# Connectors.net
KiCad netlist of a schematic drawn in Altium Designer
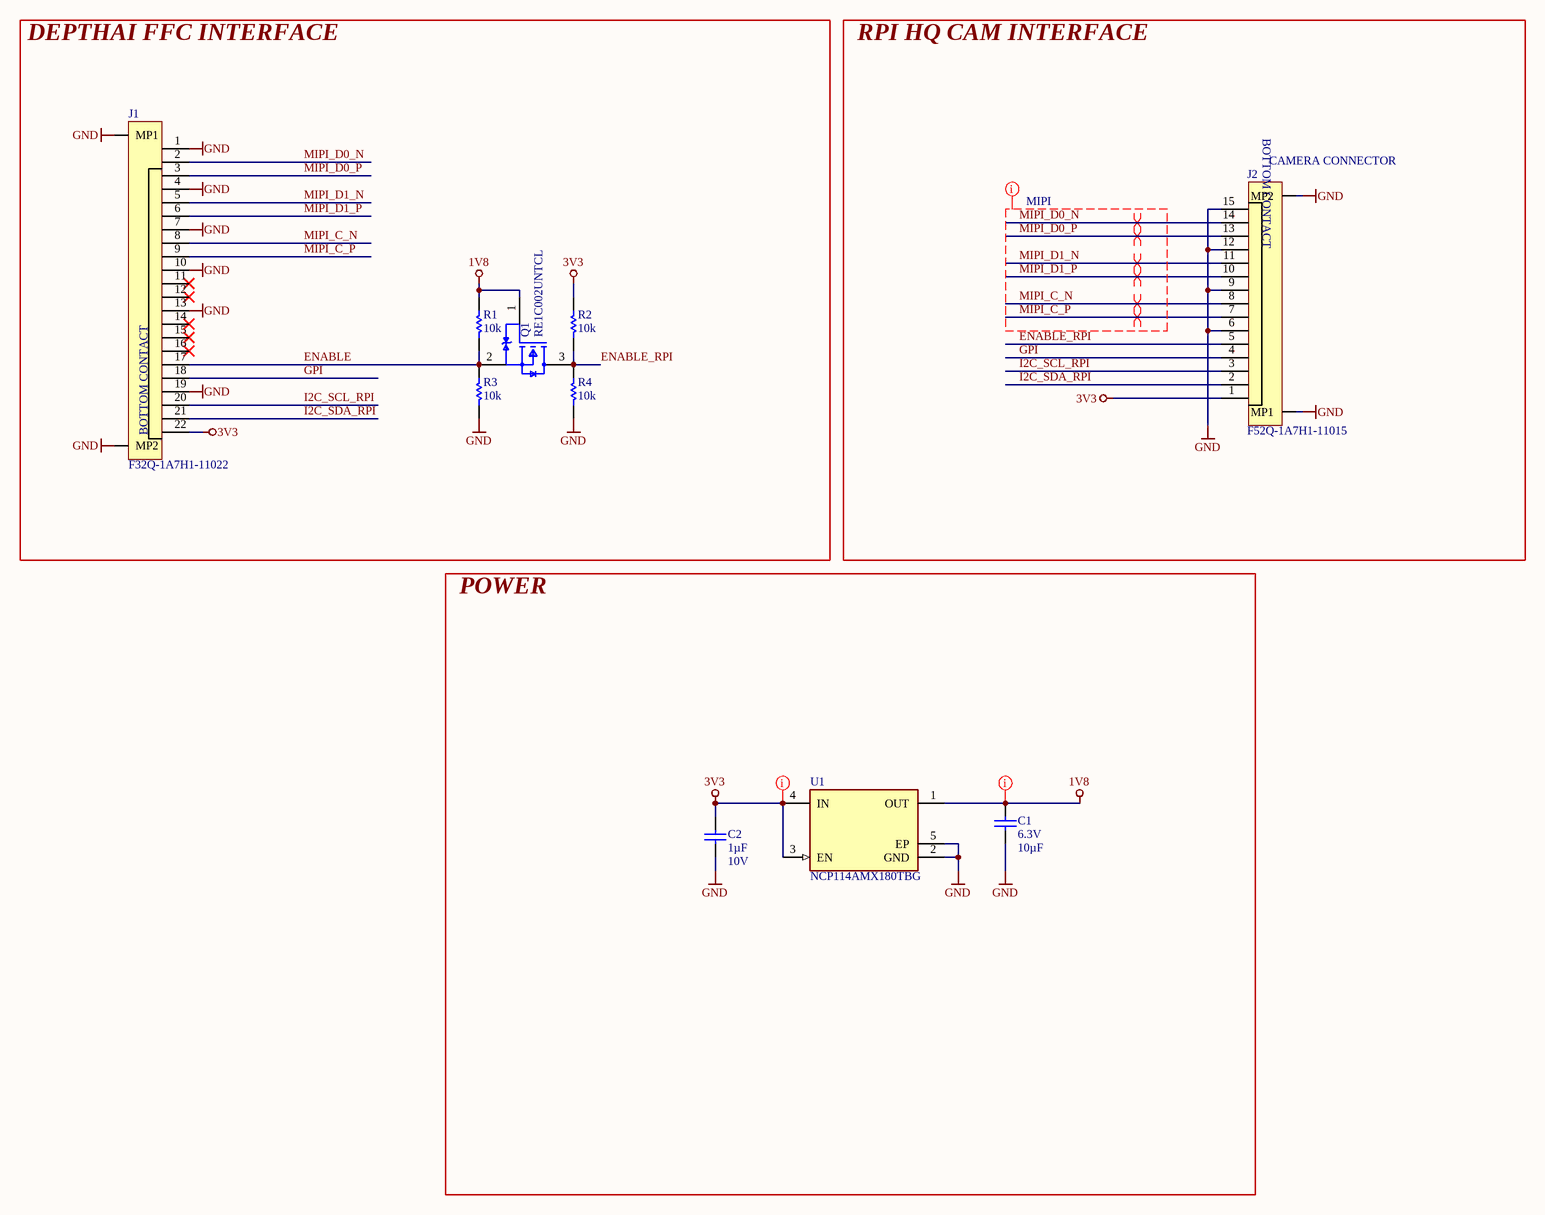
[diagram p0: Connectors.SchDoc]

(export (version "E")
  (design (tool "Eeschema 10.0.6"))
  (components
    (comp (ref "C1")
      (value "10µF")
      (footprint "CAPC0402(1005)70_L")
      (description "CAP CER 10UF 6.3V X5R 0402 20%")
      (fields
        (field (name "TOLERANCE") "20%")
        (field (name "VOLTAGE RATING") "6.3V")
        (field (name "Comment") "GRM155R60J106ME15D")
      )
      (libsource (lib "Luxonis LLC") (part "LLL153C70G474ME17E"))
    )
    (comp (ref "C2")
      (value "1µF")
      (footprint "CAPC0201(0603)33_L")
      (description "CAP CER 1UF 10V X5R 0201 20%")
      (fields
        (field (name "VOLTAGE RATING") "10V")
        (field (name "TOLERANCE") "20%")
        (field (name "Comment") "GRM033R61A105ME15D")
      )
      (libsource (lib "Luxonis LLC") (part "LLL153C70G474ME17E"))
    )
    (comp (ref "J1")
      (value "F32Q-1A7H1-11022")
      (footprint "F32Q-1A7H1-11022")
      (description "FPC/FFC Connector Socket 22 Position 0.5mm Top Contact Solder Right Angle Surface Mount T/R")
      (libsource (lib "Luxonis LLC") (part "F32R-1A7H1-11022"))
    )
    (comp (ref "J2")
      (value "F52Q-1A7H1-11015")
      (footprint "F52Q-1A7H1-11015-Footprint-1")
      (description "FPC/FFC Connector Socket 15 Position 1mm Top Contact Solder Right Angle Surface Mount T/R")
      (libsource (lib "Luxonis LLC") (part "F52Q-1A7H1-11015-Symbol-1"))
    )
    (comp (ref "Q1")
      (value "RE1C002UNTCL")
      (footprint "RE1C002UNTCL")
      (description "MOSFET N-CH 20V 0.2A EMT3")
      (libsource (lib "Luxonis LLC") (part "RE1C002UNTCL"))
    )
    (comp (ref "R1")
      (value "10k")
      (footprint "RESC0402(1005)_L")
      (description "RES SMD 10K OHM 1% 1/16W 0402")
      (fields (field (name "TOLERANCE") "1%") (field (name "Comment") "RC0402FR-1310KL"))
      (libsource (lib "Luxonis LLC") (part "RC0402FR-0722RL_1"))
    )
    (comp (ref "R2")
      (value "10k")
      (footprint "RESC0402(1005)_L")
      (description "RES SMD 10K OHM 1% 1/16W 0402")
      (fields (field (name "TOLERANCE") "1%") (field (name "Comment") "RC0402FR-1310KL"))
      (libsource (lib "Luxonis LLC") (part "RC0402FR-0722RL_1"))
    )
    (comp (ref "R3")
      (value "10k")
      (footprint "RESC0402(1005)_L")
      (description "RES SMD 10K OHM 1% 1/16W 0402")
      (fields (field (name "TOLERANCE") "1%") (field (name "Comment") "RC0402FR-1310KL"))
      (libsource (lib "Luxonis LLC") (part "RC0402FR-0722RL_1"))
    )
    (comp (ref "R4")
      (value "10k")
      (footprint "RESC0402(1005)_L")
      (description "RES SMD 10K OHM 1% 1/16W 0402")
      (fields (field (name "TOLERANCE") "1%") (field (name "Comment") "RC0402FR-1310KL"))
      (libsource (lib "Luxonis LLC") (part "RC0402FR-0722RL_1"))
    )
    (comp (ref "U1")
      (value "NCP114AMX180TBG")
      (footprint "FP-517CU-MFG")
      (description "LDO Voltage Regulators 300 MA CMOS LDO AD O")
      (libsource (lib "Luxonis LLC") (part "d482fde4c46c8d3b68fd86b21119a5c"))
    )
  )
  (nets
    (net (code "1") (name "/ENABLE") (class "Default")
      (node (ref "J1") (pin "17") (pinfunction "17_17") (pintype "passive"))
      (node (ref "Q1") (pin "2") (pinfunction "Source_2") (pintype "passive"))
      (node (ref "R1") (pin "1") (pinfunction "1_1") (pintype "passive"))
      (node (ref "R3") (pin "2") (pinfunction "2_2") (pintype "passive"))
    )
    (net (code "2") (name "/ENABLE_RPI") (class "Default")
      (node (ref "J2") (pin "5") (pinfunction "5_5") (pintype "passive"))
      (node (ref "Q1") (pin "3") (pinfunction "Drain_3") (pintype "passive"))
      (node (ref "R2") (pin "1") (pinfunction "1_1") (pintype "passive"))
      (node (ref "R4") (pin "2") (pinfunction "2_2") (pintype "passive"))
    )
    (net (code "3") (name "/GPI") (class "Default")
      (node (ref "J1") (pin "18") (pinfunction "18_18") (pintype "passive"))
      (node (ref "J2") (pin "4") (pinfunction "4_4") (pintype "passive"))
    )
    (net (code "4") (name "/I2C_SCL_RPI") (class "Default")
      (node (ref "J1") (pin "20") (pinfunction "20_20") (pintype "passive"))
      (node (ref "J2") (pin "3") (pinfunction "3_3") (pintype "passive"))
    )
    (net (code "5") (name "/I2C_SDA_RPI") (class "Default")
      (node (ref "J1") (pin "21") (pinfunction "21_21") (pintype "passive"))
      (node (ref "J2") (pin "2") (pinfunction "2_2") (pintype "passive"))
    )
    (net (code "6") (name "/MIPI_C_N") (class "Default")
      (node (ref "J1") (pin "8") (pinfunction "8_8") (pintype "passive"))
      (node (ref "J2") (pin "8") (pinfunction "8_8") (pintype "passive"))
    )
    (net (code "7") (name "/MIPI_C_P") (class "Default")
      (node (ref "J1") (pin "9") (pinfunction "9_9") (pintype "passive"))
      (node (ref "J2") (pin "7") (pinfunction "7_7") (pintype "passive"))
    )
    (net (code "8") (name "/MIPI_D0_N") (class "Default")
      (node (ref "J1") (pin "2") (pinfunction "2_2") (pintype "passive"))
      (node (ref "J2") (pin "14") (pinfunction "14_14") (pintype "passive"))
    )
    (net (code "9") (name "/MIPI_D0_P") (class "Default")
      (node (ref "J1") (pin "3") (pinfunction "3_3") (pintype "passive"))
      (node (ref "J2") (pin "13") (pinfunction "13_13") (pintype "passive"))
    )
    (net (code "10") (name "/MIPI_D1_N") (class "Default")
      (node (ref "J1") (pin "5") (pinfunction "5_5") (pintype "passive"))
      (node (ref "J2") (pin "11") (pinfunction "11_11") (pintype "passive"))
    )
    (net (code "11") (name "/MIPI_D1_P") (class "Default")
      (node (ref "J1") (pin "6") (pinfunction "6_6") (pintype "passive"))
      (node (ref "J2") (pin "10") (pinfunction "10_10") (pintype "passive"))
    )
    (net (code "12") (name "1V8") (class "Default")
      (node (ref "C1") (pin "2") (pinfunction "2_2") (pintype "passive"))
      (node (ref "Q1") (pin "1") (pinfunction "Gate_1") (pintype "passive"))
      (node (ref "R1") (pin "2") (pinfunction "2_2") (pintype "passive"))
      (node (ref "U1") (pin "1") (pinfunction "OUT_1") (pintype "power_in"))
    )
    (net (code "13") (name "3V3") (class "Default")
      (node (ref "C2") (pin "2") (pinfunction "2_2") (pintype "passive"))
      (node (ref "J1") (pin "22") (pinfunction "22_22") (pintype "passive"))
      (node (ref "J2") (pin "1") (pinfunction "1_1") (pintype "passive"))
      (node (ref "R2") (pin "2") (pinfunction "2_2") (pintype "passive"))
      (node (ref "U1") (pin "3") (pinfunction "EN_3") (pintype "input"))
      (node (ref "U1") (pin "4") (pinfunction "IN_4") (pintype "power_in"))
    )
    (net (code "14") (name "GND") (class "Default")
      (node (ref "C1") (pin "1") (pinfunction "1_1") (pintype "passive"))
      (node (ref "C2") (pin "1") (pinfunction "1_1") (pintype "passive"))
      (node (ref "J1") (pin "1") (pinfunction "1_1") (pintype "passive"))
      (node (ref "J1") (pin "10") (pinfunction "10_10") (pintype "passive"))
      (node (ref "J1") (pin "13") (pinfunction "13_13") (pintype "passive"))
      (node (ref "J1") (pin "19") (pinfunction "19_19") (pintype "passive"))
      (node (ref "J1") (pin "4") (pinfunction "4_4") (pintype "passive"))
      (node (ref "J1") (pin "7") (pinfunction "7_7") (pintype "passive"))
      (node (ref "J1") (pin "MP1") (pinfunction "MP1_MP1") (pintype "passive"))
      (node (ref "J1") (pin "MP2") (pinfunction "MP2_MP2") (pintype "passive"))
      (node (ref "J2") (pin "12") (pinfunction "12_12") (pintype "passive"))
      (node (ref "J2") (pin "15") (pinfunction "15_15") (pintype "passive"))
      (node (ref "J2") (pin "6") (pinfunction "6_6") (pintype "passive"))
      (node (ref "J2") (pin "9") (pinfunction "9_9") (pintype "passive"))
      (node (ref "J2") (pin "MP1") (pinfunction "MP1_MP1") (pintype "passive"))
      (node (ref "J2") (pin "MP2") (pinfunction "MP2_MP2") (pintype "passive"))
      (node (ref "R3") (pin "1") (pinfunction "1_1") (pintype "passive"))
      (node (ref "R4") (pin "1") (pinfunction "1_1") (pintype "passive"))
      (node (ref "U1") (pin "2") (pinfunction "GND_2") (pintype "power_in"))
      (node (ref "U1") (pin "5") (pinfunction "EP_5") (pintype "power_in"))
    )
    (net (code "15") (name "unconnected-(J1-Pad11)") (class "Default")
      (node (ref "J1") (pin "11") (pinfunction "11_11") (pintype "passive+no_connect"))
    )
    (net (code "16") (name "unconnected-(J1-Pad12)") (class "Default")
      (node (ref "J1") (pin "12") (pinfunction "12_12") (pintype "passive+no_connect"))
    )
    (net (code "17") (name "unconnected-(J1-Pad14)") (class "Default")
      (node (ref "J1") (pin "14") (pinfunction "14_14") (pintype "passive+no_connect"))
    )
    (net (code "18") (name "unconnected-(J1-Pad15)") (class "Default")
      (node (ref "J1") (pin "15") (pinfunction "15_15") (pintype "passive+no_connect"))
    )
    (net (code "19") (name "unconnected-(J1-Pad16)") (class "Default")
      (node (ref "J1") (pin "16") (pinfunction "16_16") (pintype "passive+no_connect"))
    )
  )
)
